# DC-DC_MC34063.net
KiCad netlist of a schematic drawn in Altium Designer
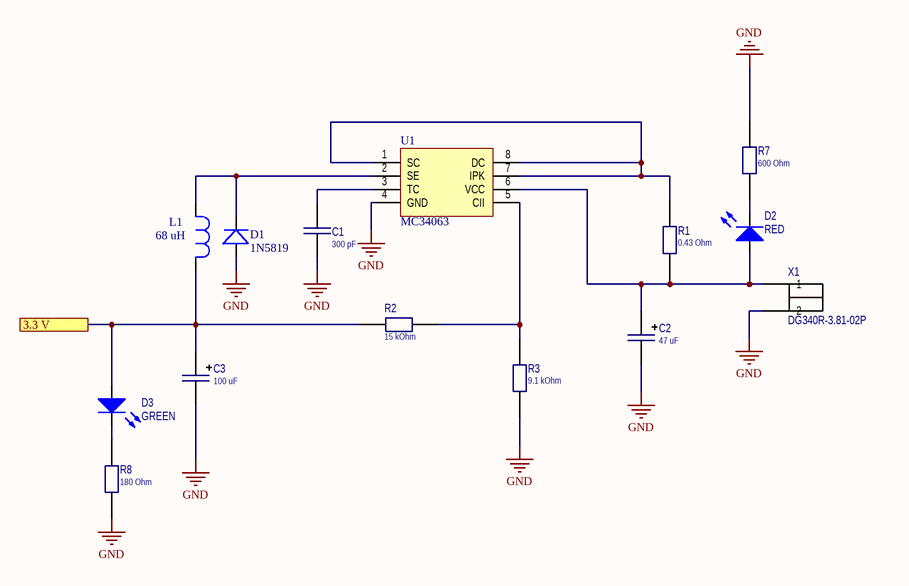
[diagram p0: DC-DC_MC34063.SchDoc]

(export (version "E")
  (design (tool "Eeschema 10.0.6"))
  (components
    (comp (ref "C1")
      (value "300 pF")
      (footprint "C_0805")
      (description "Capacitor")
      (libsource (lib "capacitors") (part "C0805"))
    )
    (comp (ref "C2")
      (value "47 uF")
      (footprint "Cap 0810 F")
      (description "Capacitor")
      (libsource (lib "capacitors") (part "CAP0810Alu"))
    )
    (comp (ref "C3")
      (value "100 uF")
      (footprint "Cap 0810 F")
      (description "Capacitor")
      (libsource (lib "capacitors") (part "CAP0810Alu"))
    )
    (comp (ref "D1") (value "1N5819") (footprint "DO-41") (libsource (lib "diode") (part "1N5819")))
    (comp (ref "D2")
      (value "RED")
      (footprint "LED_1206")
      (description "Typical INFRARED GaAs LED")
      (libsource (lib "led_lcd") (part "LED_SMT_1206"))
    )
    (comp (ref "D3")
      (value "GREEN")
      (footprint "LED_1206")
      (description "Typical INFRARED GaAs LED")
      (libsource (lib "led_lcd") (part "LED_SMT_1206"))
    )
    (comp (ref "L1")
      (value "68 uH")
      (footprint "L_1210")
      (description "Inductor")
      (fields (field (name "PART NUMBER") "NLCV32T-680K-EF"))
      (libsource (lib "inductors_transformers") (part "L1210"))
    )
    (comp (ref "R1")
      (value "0.43 Ohm")
      (footprint "R_0805")
      (description "Resistor")
      (libsource (lib "resistors") (part "R0805"))
    )
    (comp (ref "R2")
      (value "15 kOhm")
      (footprint "R_0805")
      (description "Resistor")
      (libsource (lib "resistors") (part "R0805"))
    )
    (comp (ref "R3")
      (value "9.1 kOhm")
      (footprint "R_0805")
      (description "Resistor")
      (libsource (lib "resistors") (part "R0805"))
    )
    (comp (ref "R7")
      (value "600 Ohm")
      (footprint "R_0805")
      (description "Resistor")
      (libsource (lib "resistors") (part "R0805"))
    )
    (comp (ref "R8")
      (value "180 Ohm")
      (footprint "R_0805")
      (description "Resistor")
      (libsource (lib "resistors") (part "R0805"))
    )
    (comp (ref "U1") (value "MC34063") (footprint "SO-8") (libsource (lib "dcdc_ldo_ref") (part "MC34063")))
    (comp (ref "X1")
      (value "DG340R-3.81-02P")
      (footprint "340-021-12")
      (description "Connectors")
      (fields (field (name "TYPE") "DG340R-3.81-02P"))
      (libsource (lib "connectors_socets") (part "DG340R-3.81-02P"))
    )
  )
  (nets
    (net (code "1") (name "/3.3 V") (class "Default")
      (node (ref "C3") (pin "2") (pinfunction "2_2") (pintype "passive"))
      (node (ref "D3") (pin "1") (pinfunction "A_1") (pintype "passive"))
      (node (ref "L1") (pin "2") (pintype "passive"))
      (node (ref "R2") (pin "1") (pinfunction "1_1") (pintype "passive"))
    )
    (net (code "2") (name "GND") (class "Default")
      (node (ref "C1") (pin "1") (pinfunction "1_1") (pintype "passive"))
      (node (ref "C2") (pin "1") (pinfunction "1_1") (pintype "passive"))
      (node (ref "C3") (pin "1") (pinfunction "1_1") (pintype "passive"))
      (node (ref "D1") (pin "1") (pinfunction "A_1") (pintype "passive"))
      (node (ref "R3") (pin "1") (pinfunction "1_1") (pintype "passive"))
      (node (ref "R7") (pin "2") (pinfunction "2_2") (pintype "passive"))
      (node (ref "R8") (pin "1") (pinfunction "1_1") (pintype "passive"))
      (node (ref "U1") (pin "4") (pinfunction "GND_4") (pintype "passive"))
      (node (ref "X1") (pin "2") (pinfunction "2_2") (pintype "passive"))
    )
    (net (code "3") (name "Net-(D1-K)") (class "Default")
      (node (ref "D1") (pin "2") (pinfunction "K_2") (pintype "passive"))
      (node (ref "L1") (pin "1") (pintype "passive"))
      (node (ref "U1") (pin "2") (pinfunction "SE_2") (pintype "passive"))
    )
    (net (code "4") (name "Net-(D2-A)") (class "Default")
      (node (ref "C2") (pin "2") (pinfunction "2_2") (pintype "passive"))
      (node (ref "D2") (pin "1") (pinfunction "A_1") (pintype "passive"))
      (node (ref "R1") (pin "1") (pinfunction "1_1") (pintype "passive"))
      (node (ref "U1") (pin "6") (pinfunction "VCC_6") (pintype "passive"))
      (node (ref "X1") (pin "1") (pinfunction "1_1") (pintype "passive"))
    )
    (net (code "5") (name "Net-(D2-K)") (class "Default")
      (node (ref "D2") (pin "2") (pinfunction "K_2") (pintype "passive"))
      (node (ref "R7") (pin "1") (pinfunction "1_1") (pintype "passive"))
    )
    (net (code "6") (name "Net-(D3-K)") (class "Default")
      (node (ref "D3") (pin "2") (pinfunction "K_2") (pintype "passive"))
      (node (ref "R8") (pin "2") (pinfunction "2_2") (pintype "passive"))
    )
    (net (code "7") (name "Net-(U1-CII)") (class "Default")
      (node (ref "R2") (pin "2") (pinfunction "2_2") (pintype "passive"))
      (node (ref "R3") (pin "2") (pinfunction "2_2") (pintype "passive"))
      (node (ref "U1") (pin "5") (pinfunction "CII_5") (pintype "passive"))
    )
    (net (code "8") (name "Net-(U1-DC)") (class "Default")
      (node (ref "R1") (pin "2") (pinfunction "2_2") (pintype "passive"))
      (node (ref "U1") (pin "1") (pinfunction "SC_1") (pintype "passive"))
      (node (ref "U1") (pin "7") (pinfunction "IPK_7") (pintype "passive"))
      (node (ref "U1") (pin "8") (pinfunction "DC_8") (pintype "passive"))
    )
    (net (code "9") (name "Net-(U1-TC)") (class "Default")
      (node (ref "C1") (pin "2") (pinfunction "2_2") (pintype "passive"))
      (node (ref "U1") (pin "3") (pinfunction "TC_3") (pintype "passive"))
    )
  )
)
